# dc-10.net
KiCad netlist of a schematic drawn in Altium Designer
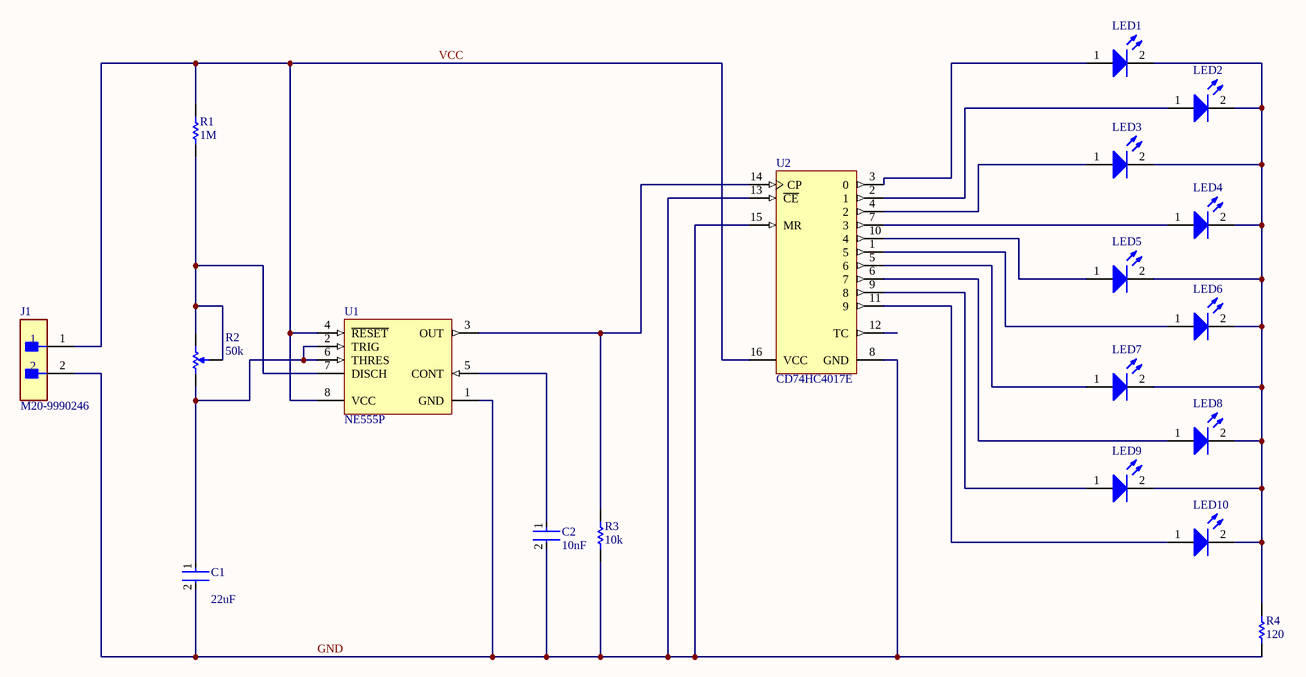
[diagram p0: dc-10.SchDoc]

(export (version "E")
  (design (tool "Eeschema 10.0.6"))
  (components
    (comp (ref "C1")
      (value "RCER71E226MWM1H03A")
      (footprint "FP-RCEWM1-MFG")
      (description "CAP CER 22UF 25V X7R RADIAL")
      (fields (field (name "CAPACITANCE") "22uF") (field (name "TOLERANCE") "20%"))
      (libsource (lib "Altium Content Vault") (part "02cd4be3c70576c341d710602a673aa"))
    )
    (comp (ref "C2")
      (value "RCER71H103K0K1H03B")
      (footprint "FP-RCE0K1-MFG")
      (description "Cap Ceramic 10nF 50V X7R ±10% Radial 5mm +125°C Automotive Bulk")
      (fields (field (name "CAPACITANCE") "10nF") (field (name "TOLERANCE") "10%"))
      (libsource (lib "Altium Content Vault") (part "b4654b650e69147ec39a6b967a45e02"))
    )
    (comp (ref "J1")
      (value "M20-9990246")
      (footprint "FP-M20-9990246-MFG")
      (description "CONN HEADER VERT 2POS 2.54MM")
      (fields
        (field (name "OCTOPART") "https://octopart.com/m20-9990246-harwin-2590635")
        (field (name "MANUFACTURER") "Harwin")
      )
      (libsource (lib "Altium Content Vault") (part "3bc925449376181038e59eaffc5286c"))
    )
    (comp (ref "LED1")
      (value "151051BS04000")
      (footprint "WL-TMRC_D5.9H8.7")
      (libsource (lib "Altium Content Vault") (part "LED_Blue_1A-2K"))
    )
    (comp (ref "LED2")
      (value "151051BS04000")
      (footprint "WL-TMRC_D5.9H8.7")
      (libsource (lib "Altium Content Vault") (part "LED_Blue_1A-2K"))
    )
    (comp (ref "LED3")
      (value "151051BS04000")
      (footprint "WL-TMRC_D5.9H8.7")
      (libsource (lib "Altium Content Vault") (part "LED_Blue_1A-2K"))
    )
    (comp (ref "LED4")
      (value "151051BS04000")
      (footprint "WL-TMRC_D5.9H8.7")
      (libsource (lib "Altium Content Vault") (part "LED_Blue_1A-2K"))
    )
    (comp (ref "LED5")
      (value "151051BS04000")
      (footprint "WL-TMRC_D5.9H8.7")
      (libsource (lib "Altium Content Vault") (part "LED_Blue_1A-2K"))
    )
    (comp (ref "LED6")
      (value "151051BS04000")
      (footprint "WL-TMRC_D5.9H8.7")
      (libsource (lib "Altium Content Vault") (part "LED_Blue_1A-2K"))
    )
    (comp (ref "LED7")
      (value "151051BS04000")
      (footprint "WL-TMRC_D5.9H8.7")
      (libsource (lib "Altium Content Vault") (part "LED_Blue_1A-2K"))
    )
    (comp (ref "LED8")
      (value "151051BS04000")
      (footprint "WL-TMRC_D5.9H8.7")
      (libsource (lib "Altium Content Vault") (part "LED_Blue_1A-2K"))
    )
    (comp (ref "LED9")
      (value "151051BS04000")
      (footprint "WL-TMRC_D5.9H8.7")
      (libsource (lib "Altium Content Vault") (part "LED_Blue_1A-2K"))
    )
    (comp (ref "LED10")
      (value "151051BS04000")
      (footprint "WL-TMRC_D5.9H8.7")
      (libsource (lib "Altium Content Vault") (part "LED_Blue_1A-2K"))
    )
    (comp (ref "R1")
      (value "MFR-25FBF52-1M")
      (footprint "RESA60-630X240")
      (description "Axial Resistor, 1 MOhm, +/- 1%, 250 mW, -55 to 155 degC, 2-Pin THD, RoHS, Bulk")
      (fields (field (name "RESISTANCE") "1M") (field (name "TOLERANCE") "1%"))
      (libsource (lib "Altium Content Vault") (part "RES-2"))
    )
    (comp (ref "R2")
      (value "3313J-1-503E")
      (footprint "BOUR-3313J-1_V")
      (fields (field (name "MANUFACTURER") "Bourns") (field (name "TRACK RESISTANCE") "50k"))
      (libsource (lib "Altium Content Vault") (part "RES-ADJ-3_A"))
    )
    (comp (ref "R3")
      (value "OD103JE")
      (footprint "OMTE-RES7X2.5-2")
      (fields
        (field (name "RESISTANCE (OHMS)") "10k")
        (field (name "TOLERANCE") "±5%")
        (field (name "MANUFACTURER") "Ohmite")
      )
      (libsource (lib "Altium Content Vault") (part "RES-2"))
    )
    (comp (ref "R4")
      (value "OD103JE")
      (footprint "OMTE-RES7X2.5-2")
      (fields
        (field (name "RESISTANCE (OHMS)") "120")
        (field (name "TOLERANCE") "±5%")
        (field (name "MANUFACTURER") "Ohmite")
      )
      (libsource (lib "Altium Content Vault") (part "RES-2"))
    )
    (comp (ref "U1")
      (value "NE555P")
      (footprint "P0008A")
      (description "Precision Timer, 4.5 to 16 V, 0 to 70 degC, 8-Pin DIP, Pb-Free, Tube")
      (fields (field (name "MANUFACTURER") "TexasInstruments"))
      (libsource (lib "Altium Content Vault") (part "TI-NE555-P8"))
    )
    (comp (ref "U2")
      (value "CD74HC4017E")
      (footprint "N0016A")
      (description "High Speed CMOS Logic Decade Counter/Divider with 10 Decoded Outputs, N0016A, TUBE")
      (fields
        (field (name "GENERIC PART NUMBER") "CD74HC4017")
        (field (name "MANUFACTURER") "Texas Instruments")
      )
      (libsource (lib "Altium Content Vault") (part "TI-CD74HC4017-16"))
    )
  )
  (nets
    (net (code "1") (name "/GND") (class "Default")
      (node (ref "C1") (pin "2") (pinfunction "2_2") (pintype "passive"))
      (node (ref "C2") (pin "2") (pinfunction "2_2") (pintype "passive"))
      (node (ref "J1") (pin "2") (pinfunction "2_2") (pintype "passive"))
      (node (ref "R3") (pin "1") (pinfunction "1_1") (pintype "passive"))
      (node (ref "R4") (pin "1") (pinfunction "1_1") (pintype "passive"))
      (node (ref "U1") (pin "1") (pinfunction "GND_1") (pintype "power_in"))
      (node (ref "U2") (pin "13") (pinfunction "~{CE}_13") (pintype "input"))
      (node (ref "U2") (pin "15") (pinfunction "MR_15") (pintype "input"))
      (node (ref "U2") (pin "8") (pinfunction "GND_8") (pintype "power_in"))
    )
    (net (code "2") (name "/VCC") (class "Default")
      (node (ref "J1") (pin "1") (pinfunction "1_1") (pintype "passive"))
      (node (ref "R1") (pin "2") (pinfunction "2_2") (pintype "passive"))
      (node (ref "U1") (pin "4") (pinfunction "~{RESET}_4") (pintype "input"))
      (node (ref "U1") (pin "8") (pinfunction "VCC_8") (pintype "power_in"))
      (node (ref "U2") (pin "16") (pinfunction "VCC_16") (pintype "power_in"))
    )
    (net (code "3") (name "Net-(LED1-A)") (class "Default")
      (node (ref "LED1") (pin "1") (pinfunction "A_1") (pintype "passive"))
      (node (ref "U2") (pin "3") (pinfunction "0_3") (pintype "output"))
    )
    (net (code "4") (name "Net-(LED1-K)") (class "Default")
      (node (ref "LED1") (pin "2") (pinfunction "K_2") (pintype "passive"))
      (node (ref "LED10") (pin "2") (pinfunction "K_2") (pintype "passive"))
      (node (ref "LED2") (pin "2") (pinfunction "K_2") (pintype "passive"))
      (node (ref "LED3") (pin "2") (pinfunction "K_2") (pintype "passive"))
      (node (ref "LED4") (pin "2") (pinfunction "K_2") (pintype "passive"))
      (node (ref "LED5") (pin "2") (pinfunction "K_2") (pintype "passive"))
      (node (ref "LED6") (pin "2") (pinfunction "K_2") (pintype "passive"))
      (node (ref "LED7") (pin "2") (pinfunction "K_2") (pintype "passive"))
      (node (ref "LED8") (pin "2") (pinfunction "K_2") (pintype "passive"))
      (node (ref "LED9") (pin "2") (pinfunction "K_2") (pintype "passive"))
      (node (ref "R4") (pin "2") (pinfunction "2_2") (pintype "passive"))
    )
    (net (code "5") (name "Net-(LED2-A)") (class "Default")
      (node (ref "LED2") (pin "1") (pinfunction "A_1") (pintype "passive"))
      (node (ref "U2") (pin "2") (pinfunction "1_2") (pintype "output"))
    )
    (net (code "6") (name "Net-(LED3-A)") (class "Default")
      (node (ref "LED3") (pin "1") (pinfunction "A_1") (pintype "passive"))
      (node (ref "U2") (pin "4") (pinfunction "2_4") (pintype "output"))
    )
    (net (code "7") (name "Net-(LED4-A)") (class "Default")
      (node (ref "LED4") (pin "1") (pinfunction "A_1") (pintype "passive"))
      (node (ref "U2") (pin "7") (pinfunction "3_7") (pintype "output"))
    )
    (net (code "8") (name "Net-(LED5-A)") (class "Default")
      (node (ref "LED5") (pin "1") (pinfunction "A_1") (pintype "passive"))
      (node (ref "U2") (pin "10") (pinfunction "4_10") (pintype "output"))
    )
    (net (code "9") (name "Net-(LED6-A)") (class "Default")
      (node (ref "LED6") (pin "1") (pinfunction "A_1") (pintype "passive"))
      (node (ref "U2") (pin "1") (pinfunction "5_1") (pintype "output"))
    )
    (net (code "10") (name "Net-(LED7-A)") (class "Default")
      (node (ref "LED7") (pin "1") (pinfunction "A_1") (pintype "passive"))
      (node (ref "U2") (pin "5") (pinfunction "6_5") (pintype "output"))
    )
    (net (code "11") (name "Net-(LED8-A)") (class "Default")
      (node (ref "LED8") (pin "1") (pinfunction "A_1") (pintype "passive"))
      (node (ref "U2") (pin "6") (pinfunction "7_6") (pintype "output"))
    )
    (net (code "12") (name "Net-(LED9-A)") (class "Default")
      (node (ref "LED9") (pin "1") (pinfunction "A_1") (pintype "passive"))
      (node (ref "U2") (pin "9") (pinfunction "8_9") (pintype "output"))
    )
    (net (code "13") (name "Net-(LED10-A)") (class "Default")
      (node (ref "LED10") (pin "1") (pinfunction "A_1") (pintype "passive"))
      (node (ref "U2") (pin "11") (pinfunction "9_11") (pintype "output"))
    )
    (net (code "14") (name "Net-(U1-CONT)") (class "Default")
      (node (ref "C2") (pin "1") (pinfunction "1_1") (pintype "passive"))
      (node (ref "U1") (pin "5") (pinfunction "CONT_5") (pintype "input"))
    )
    (net (code "15") (name "Net-(U1-DISCH)") (class "Default")
      (node (ref "R1") (pin "1") (pinfunction "1_1") (pintype "passive"))
      (node (ref "R2") (pin "2") (pinfunction "2_2") (pintype "passive"))
      (node (ref "R2") (pin "3") (pinfunction "3_3") (pintype "passive"))
      (node (ref "U1") (pin "7") (pinfunction "DISCH_7") (pintype "open_collector"))
    )
    (net (code "16") (name "Net-(U1-OUT)") (class "Default")
      (node (ref "R3") (pin "2") (pinfunction "2_2") (pintype "passive"))
      (node (ref "U1") (pin "3") (pinfunction "OUT_3") (pintype "output"))
      (node (ref "U2") (pin "14") (pinfunction "CP_14") (pintype "input"))
    )
    (net (code "17") (name "Net-(U1-THRES)") (class "Default")
      (node (ref "C1") (pin "1") (pinfunction "1_1") (pintype "passive"))
      (node (ref "R2") (pin "1") (pinfunction "1_1") (pintype "passive"))
      (node (ref "U1") (pin "2") (pinfunction "TRIG_2") (pintype "input"))
      (node (ref "U1") (pin "6") (pinfunction "THRES_6") (pintype "input"))
    )
    (net (code "18") (name "unconnected-(U2-TC-Pad12)") (class "Default")
      (node (ref "U2") (pin "12") (pinfunction "TC_12") (pintype "output"))
    )
  )
)
